# mounted_temp_sensor_breakout_board_V1.net
KiCad netlist of a schematic drawn in EAGLE
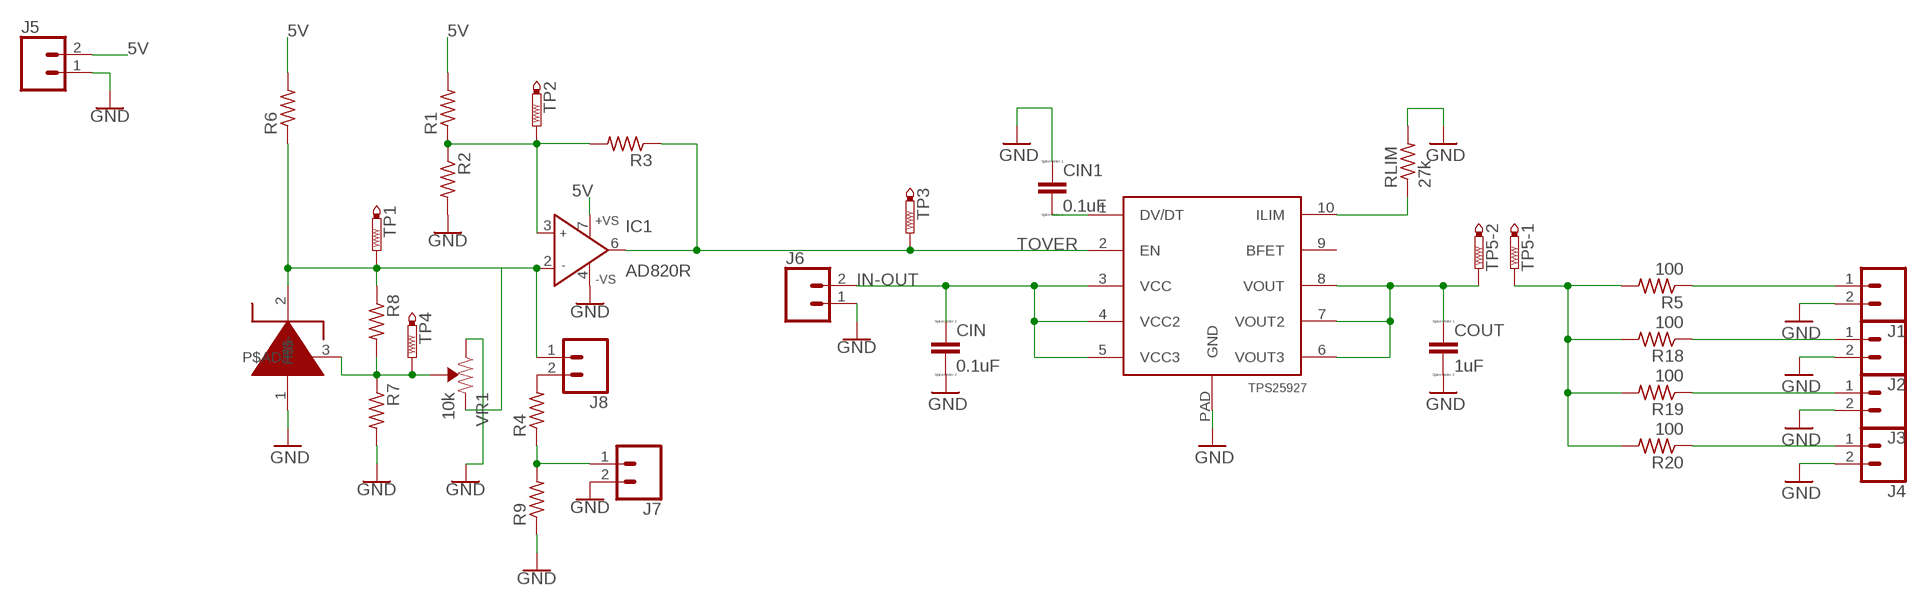
[diagram p0: schematic, sheet 1]

(export (version "E")
  (design (tool "Eeschema 10.0.6"))
  (components
    (comp (ref "CIN")
      (value "0.1uF")
      (footprint "eagle-import:C0805")
      (libsource (lib "eagle-import") (part "C"))
    )
    (comp (ref "CIN1")
      (value "0.1uF")
      (footprint "eagle-import:C0805")
      (libsource (lib "eagle-import") (part "C"))
    )
    (comp (ref "COUT")
      (value "1uF")
      (footprint "eagle-import:C0805")
      (libsource (lib "eagle-import") (part "C"))
    )
    (comp (ref "IC1")
      (value "AD820R")
      (footprint "eagle-import:SO8")
      (libsource (lib "eagle-import") (part "AD820R"))
    )
    (comp (ref "J1")
      (value "CONN_02PTH4")
      (footprint "eagle-import:1X02_XTRA_BIG")
      (libsource (lib "eagle-import") (part "CONN_02PTH4"))
    )
    (comp (ref "J2")
      (value "CONN_02PTH4")
      (footprint "eagle-import:1X02_XTRA_BIG")
      (libsource (lib "eagle-import") (part "CONN_02PTH4"))
    )
    (comp (ref "J3")
      (value "CONN_02PTH4")
      (footprint "eagle-import:1X02_XTRA_BIG")
      (libsource (lib "eagle-import") (part "CONN_02PTH4"))
    )
    (comp (ref "J4")
      (value "CONN_02PTH4")
      (footprint "eagle-import:1X02_XTRA_BIG")
      (libsource (lib "eagle-import") (part "CONN_02PTH4"))
    )
    (comp (ref "J5")
      (value "CONN_02PTH4")
      (footprint "eagle-import:1X02_XTRA_BIG")
      (libsource (lib "eagle-import") (part "CONN_02PTH4"))
    )
    (comp (ref "J6")
      (value "CONN_02PTH4")
      (footprint "eagle-import:1X02_XTRA_BIG")
      (libsource (lib "eagle-import") (part "CONN_02PTH4"))
    )
    (comp (ref "J7")
      (value "CONN_02PTH3")
      (footprint "eagle-import:1X02_LONGPADS")
      (libsource (lib "eagle-import") (part "CONN_02PTH3"))
    )
    (comp (ref "J8")
      (value "CONN_02")
      (footprint "eagle-import:1X02")
      (libsource (lib "eagle-import") (part "CONN_02"))
    )
    (comp (ref "R1")
      (value "R-US_R0805")
      (footprint "eagle-import:R0805")
      (libsource (lib "eagle-import") (part "R-US_R0805"))
    )
    (comp (ref "R2")
      (value "R-US_R0805")
      (footprint "eagle-import:R0805")
      (libsource (lib "eagle-import") (part "R-US_R0805"))
    )
    (comp (ref "R3")
      (value "R-US_R0805")
      (footprint "eagle-import:R0805")
      (libsource (lib "eagle-import") (part "R-US_R0805"))
    )
    (comp (ref "R4")
      (value "R-US_R0805")
      (footprint "eagle-import:R0805")
      (libsource (lib "eagle-import") (part "R-US_R0805"))
    )
    (comp (ref "R5")
      (value "100")
      (footprint "eagle-import:R0805")
      (libsource (lib "eagle-import") (part "R-US_R0805"))
    )
    (comp (ref "R6")
      (value "R-US_R0805")
      (footprint "eagle-import:R0805")
      (libsource (lib "eagle-import") (part "R-US_R0805"))
    )
    (comp (ref "R7")
      (value "R-US_R0805")
      (footprint "eagle-import:R0805")
      (libsource (lib "eagle-import") (part "R-US_R0805"))
    )
    (comp (ref "R8")
      (value "R-US_R0805")
      (footprint "eagle-import:R0805")
      (libsource (lib "eagle-import") (part "R-US_R0805"))
    )
    (comp (ref "R9")
      (value "R-US_R0805")
      (footprint "eagle-import:R0805")
      (libsource (lib "eagle-import") (part "R-US_R0805"))
    )
    (comp (ref "R18")
      (value "100")
      (footprint "eagle-import:R0805")
      (libsource (lib "eagle-import") (part "R-US_R0805"))
    )
    (comp (ref "R19")
      (value "100")
      (footprint "eagle-import:R0805")
      (libsource (lib "eagle-import") (part "R-US_R0805"))
    )
    (comp (ref "R20")
      (value "100")
      (footprint "eagle-import:R0805")
      (libsource (lib "eagle-import") (part "R-US_R0805"))
    )
    (comp (ref "RLIM")
      (value "27k")
      (footprint "eagle-import:R0805")
      (libsource (lib "eagle-import") (part "R-US_R0805"))
    )
    (comp (ref "TP1")
      (value "PTR1PAD1-13Y")
      (footprint "eagle-import:P1-13Y")
      (libsource (lib "eagle-import") (part "PTR1PAD1-13Y"))
    )
    (comp (ref "TP2")
      (value "PTR1PAD1-13Y")
      (footprint "eagle-import:P1-13Y")
      (libsource (lib "eagle-import") (part "PTR1PAD1-13Y"))
    )
    (comp (ref "TP3")
      (value "PTR1PAD1-13Y")
      (footprint "eagle-import:P1-13Y")
      (libsource (lib "eagle-import") (part "PTR1PAD1-13Y"))
    )
    (comp (ref "TP4")
      (value "PTR1PAD1-13Y")
      (footprint "eagle-import:P1-13Y")
      (libsource (lib "eagle-import") (part "PTR1PAD1-13Y"))
    )
    (comp (ref "TP5")
      (value "PTR2")
      (footprint "eagle-import:P2-38-17")
      (libsource (lib "eagle-import") (part "PTR2"))
    )
    (comp (ref "U$1")
      (value "LM135Z")
      (footprint "eagle-import:TO-92-3")
      (libsource (lib "eagle-import") (part "LM135Z"))
    )
    (comp (ref "U$5")
      (value "TPS252927")
      (footprint "eagle-import:VSON10")
      (libsource (lib "eagle-import") (part "TPS252927"))
    )
    (comp (ref "VR1")
      (value "10k")
      (footprint "eagle-import:TRIMPOT-SMD-TC33X")
      (libsource (lib "eagle-import") (part "TRIMPOT-SMD-3MM-OPEN-1/10W-25%"))
    )
  )
  (nets
    (net (code "1") (name "/5V") (class "Default")
      (node (ref "IC1") (pin "7") (pinfunction "+VS_7") (pintype "input"))
      (node (ref "J5") (pin "2") (pinfunction "2_2") (pintype "passive"))
      (node (ref "R1") (pin "2") (pinfunction "2_2") (pintype "passive"))
      (node (ref "R6") (pin "2") (pinfunction "2_2") (pintype "passive"))
    )
    (net (code "2") (name "/IN-OUT") (class "Default")
      (node (ref "CIN") (pin "1") (pinfunction "1_1") (pintype "passive"))
      (node (ref "J6") (pin "2") (pinfunction "2_2") (pintype "passive"))
      (node (ref "U$5") (pin "3") (pinfunction "VCC_3") (pintype "bidirectional"))
      (node (ref "U$5") (pin "4") (pinfunction "VCC2_4") (pintype "bidirectional"))
      (node (ref "U$5") (pin "5") (pinfunction "VCC3_5") (pintype "bidirectional"))
    )
    (net (code "3") (name "/TOVER") (class "Default")
      (node (ref "IC1") (pin "6") (pinfunction "OUT_6") (pintype "output"))
      (node (ref "R3") (pin "1") (pinfunction "1_1") (pintype "passive"))
      (node (ref "TP3") (pin "TP") (pinfunction "TP_TP") (pintype "input"))
      (node (ref "U$5") (pin "2") (pinfunction "EN_2") (pintype "bidirectional"))
    )
    (net (code "4") (name "GND") (class "Default")
      (node (ref "CIN") (pin "2") (pinfunction "2_2") (pintype "passive"))
      (node (ref "CIN1") (pin "1") (pinfunction "1_1") (pintype "passive"))
      (node (ref "COUT") (pin "2") (pinfunction "2_2") (pintype "passive"))
      (node (ref "IC1") (pin "4") (pinfunction "-VS_4") (pintype "input"))
      (node (ref "J1") (pin "2") (pinfunction "2_2") (pintype "passive"))
      (node (ref "J2") (pin "2") (pinfunction "2_2") (pintype "passive"))
      (node (ref "J3") (pin "2") (pinfunction "2_2") (pintype "passive"))
      (node (ref "J4") (pin "2") (pinfunction "2_2") (pintype "passive"))
      (node (ref "J5") (pin "1") (pinfunction "1_1") (pintype "passive"))
      (node (ref "J6") (pin "1") (pinfunction "1_1") (pintype "passive"))
      (node (ref "J7") (pin "2") (pinfunction "2_2") (pintype "passive"))
      (node (ref "R2") (pin "2") (pinfunction "2_2") (pintype "passive"))
      (node (ref "R7") (pin "2") (pinfunction "2_2") (pintype "passive"))
      (node (ref "R9") (pin "1") (pinfunction "1_1") (pintype "passive"))
      (node (ref "RLIM") (pin "2") (pinfunction "2_2") (pintype "passive"))
      (node (ref "U$1") (pin "1") (pinfunction "P$-_1") (pintype "bidirectional"))
      (node (ref "U$5") (pin "PAD") (pinfunction "GND_PAD") (pintype "bidirectional"))
      (node (ref "VR1") (pin "1") (pinfunction "CW_1") (pintype "passive"))
    )
    (net (code "5") (name "Net-(IC1-IN+)") (class "Default")
      (node (ref "IC1") (pin "3") (pinfunction "IN+_3") (pintype "input"))
      (node (ref "R1") (pin "1") (pinfunction "1_1") (pintype "passive"))
      (node (ref "R2") (pin "1") (pinfunction "1_1") (pintype "passive"))
      (node (ref "R3") (pin "2") (pinfunction "2_2") (pintype "passive"))
      (node (ref "TP2") (pin "TP") (pinfunction "TP_TP") (pintype "input"))
    )
    (net (code "6") (name "Net-(IC1-IN-)") (class "Default")
      (node (ref "IC1") (pin "2") (pinfunction "IN-_2") (pintype "input"))
      (node (ref "J8") (pin "1") (pinfunction "1_1") (pintype "passive"))
      (node (ref "R6") (pin "1") (pinfunction "1_1") (pintype "passive"))
      (node (ref "R8") (pin "1") (pinfunction "1_1") (pintype "passive"))
      (node (ref "TP1") (pin "TP") (pinfunction "TP_TP") (pintype "input"))
      (node (ref "U$1") (pin "2") (pinfunction "P$+_2") (pintype "bidirectional"))
      (node (ref "VR1") (pin "3") (pinfunction "CCW_3") (pintype "passive"))
    )
    (net (code "7") (name "Net-(J1-Pad1)") (class "Default")
      (node (ref "J1") (pin "1") (pinfunction "1_1") (pintype "passive"))
      (node (ref "R5") (pin "1") (pinfunction "1_1") (pintype "passive"))
    )
    (net (code "8") (name "Net-(J2-Pad1)") (class "Default")
      (node (ref "J2") (pin "1") (pinfunction "1_1") (pintype "passive"))
      (node (ref "R18") (pin "1") (pinfunction "1_1") (pintype "passive"))
    )
    (net (code "9") (name "Net-(J3-Pad1)") (class "Default")
      (node (ref "J3") (pin "1") (pinfunction "1_1") (pintype "passive"))
      (node (ref "R19") (pin "1") (pinfunction "1_1") (pintype "passive"))
    )
    (net (code "10") (name "Net-(J4-Pad1)") (class "Default")
      (node (ref "J4") (pin "1") (pinfunction "1_1") (pintype "passive"))
      (node (ref "R20") (pin "1") (pinfunction "1_1") (pintype "passive"))
    )
    (net (code "11") (name "Net-(J7-Pad1)") (class "Default")
      (node (ref "J7") (pin "1") (pinfunction "1_1") (pintype "passive"))
      (node (ref "R4") (pin "1") (pinfunction "1_1") (pintype "passive"))
      (node (ref "R9") (pin "2") (pinfunction "2_2") (pintype "passive"))
    )
    (net (code "12") (name "Net-(J8-Pad2)") (class "Default")
      (node (ref "J8") (pin "2") (pinfunction "2_2") (pintype "passive"))
      (node (ref "R4") (pin "2") (pinfunction "2_2") (pintype "passive"))
    )
    (net (code "13") (name "Net-(TP5A-TP)") (class "Default")
      (node (ref "R18") (pin "2") (pinfunction "2_2") (pintype "passive"))
      (node (ref "R19") (pin "2") (pinfunction "2_2") (pintype "passive"))
      (node (ref "R20") (pin "2") (pinfunction "2_2") (pintype "passive"))
      (node (ref "R5") (pin "2") (pinfunction "2_2") (pintype "passive"))
      (node (ref "TP5") (pin "TP-1") (pinfunction "TP_TP-1") (pintype "input"))
    )
    (net (code "14") (name "Net-(TP5B-TP)") (class "Default")
      (node (ref "COUT") (pin "1") (pinfunction "1_1") (pintype "passive"))
      (node (ref "TP5") (pin "TP-2") (pinfunction "TP_TP-2") (pintype "input"))
      (node (ref "U$5") (pin "6") (pinfunction "VOUT3_6") (pintype "bidirectional"))
      (node (ref "U$5") (pin "7") (pinfunction "VOUT2_7") (pintype "bidirectional"))
      (node (ref "U$5") (pin "8") (pinfunction "VOUT_8") (pintype "bidirectional"))
    )
    (net (code "15") (name "Net-(U$1-P$ADJ)") (class "Default")
      (node (ref "R7") (pin "1") (pinfunction "1_1") (pintype "passive"))
      (node (ref "R8") (pin "2") (pinfunction "2_2") (pintype "passive"))
      (node (ref "TP4") (pin "TP") (pinfunction "TP_TP") (pintype "input"))
      (node (ref "U$1") (pin "3") (pinfunction "P$ADJ_3") (pintype "bidirectional"))
      (node (ref "VR1") (pin "2") (pinfunction "WIPER_2") (pintype "passive"))
    )
    (net (code "16") (name "Net-(U$5-DV{slash}DT)") (class "Default")
      (node (ref "CIN1") (pin "2") (pinfunction "2_2") (pintype "passive"))
      (node (ref "U$5") (pin "1") (pinfunction "DV/DT_1") (pintype "bidirectional"))
    )
    (net (code "17") (name "Net-(U$5-ILIM)") (class "Default")
      (node (ref "RLIM") (pin "1") (pinfunction "1_1") (pintype "passive"))
      (node (ref "U$5") (pin "10") (pinfunction "ILIM_10") (pintype "bidirectional"))
    )
    (net (code "18") (name "unconnected-(U$5-BFET-Pad9)") (class "Default")
      (node (ref "U$5") (pin "9") (pinfunction "BFET_9") (pintype "bidirectional"))
    )
  )
)
